# Sitara_IO_Bank_123.net
KiCad netlist of a schematic drawn in Altium Designer
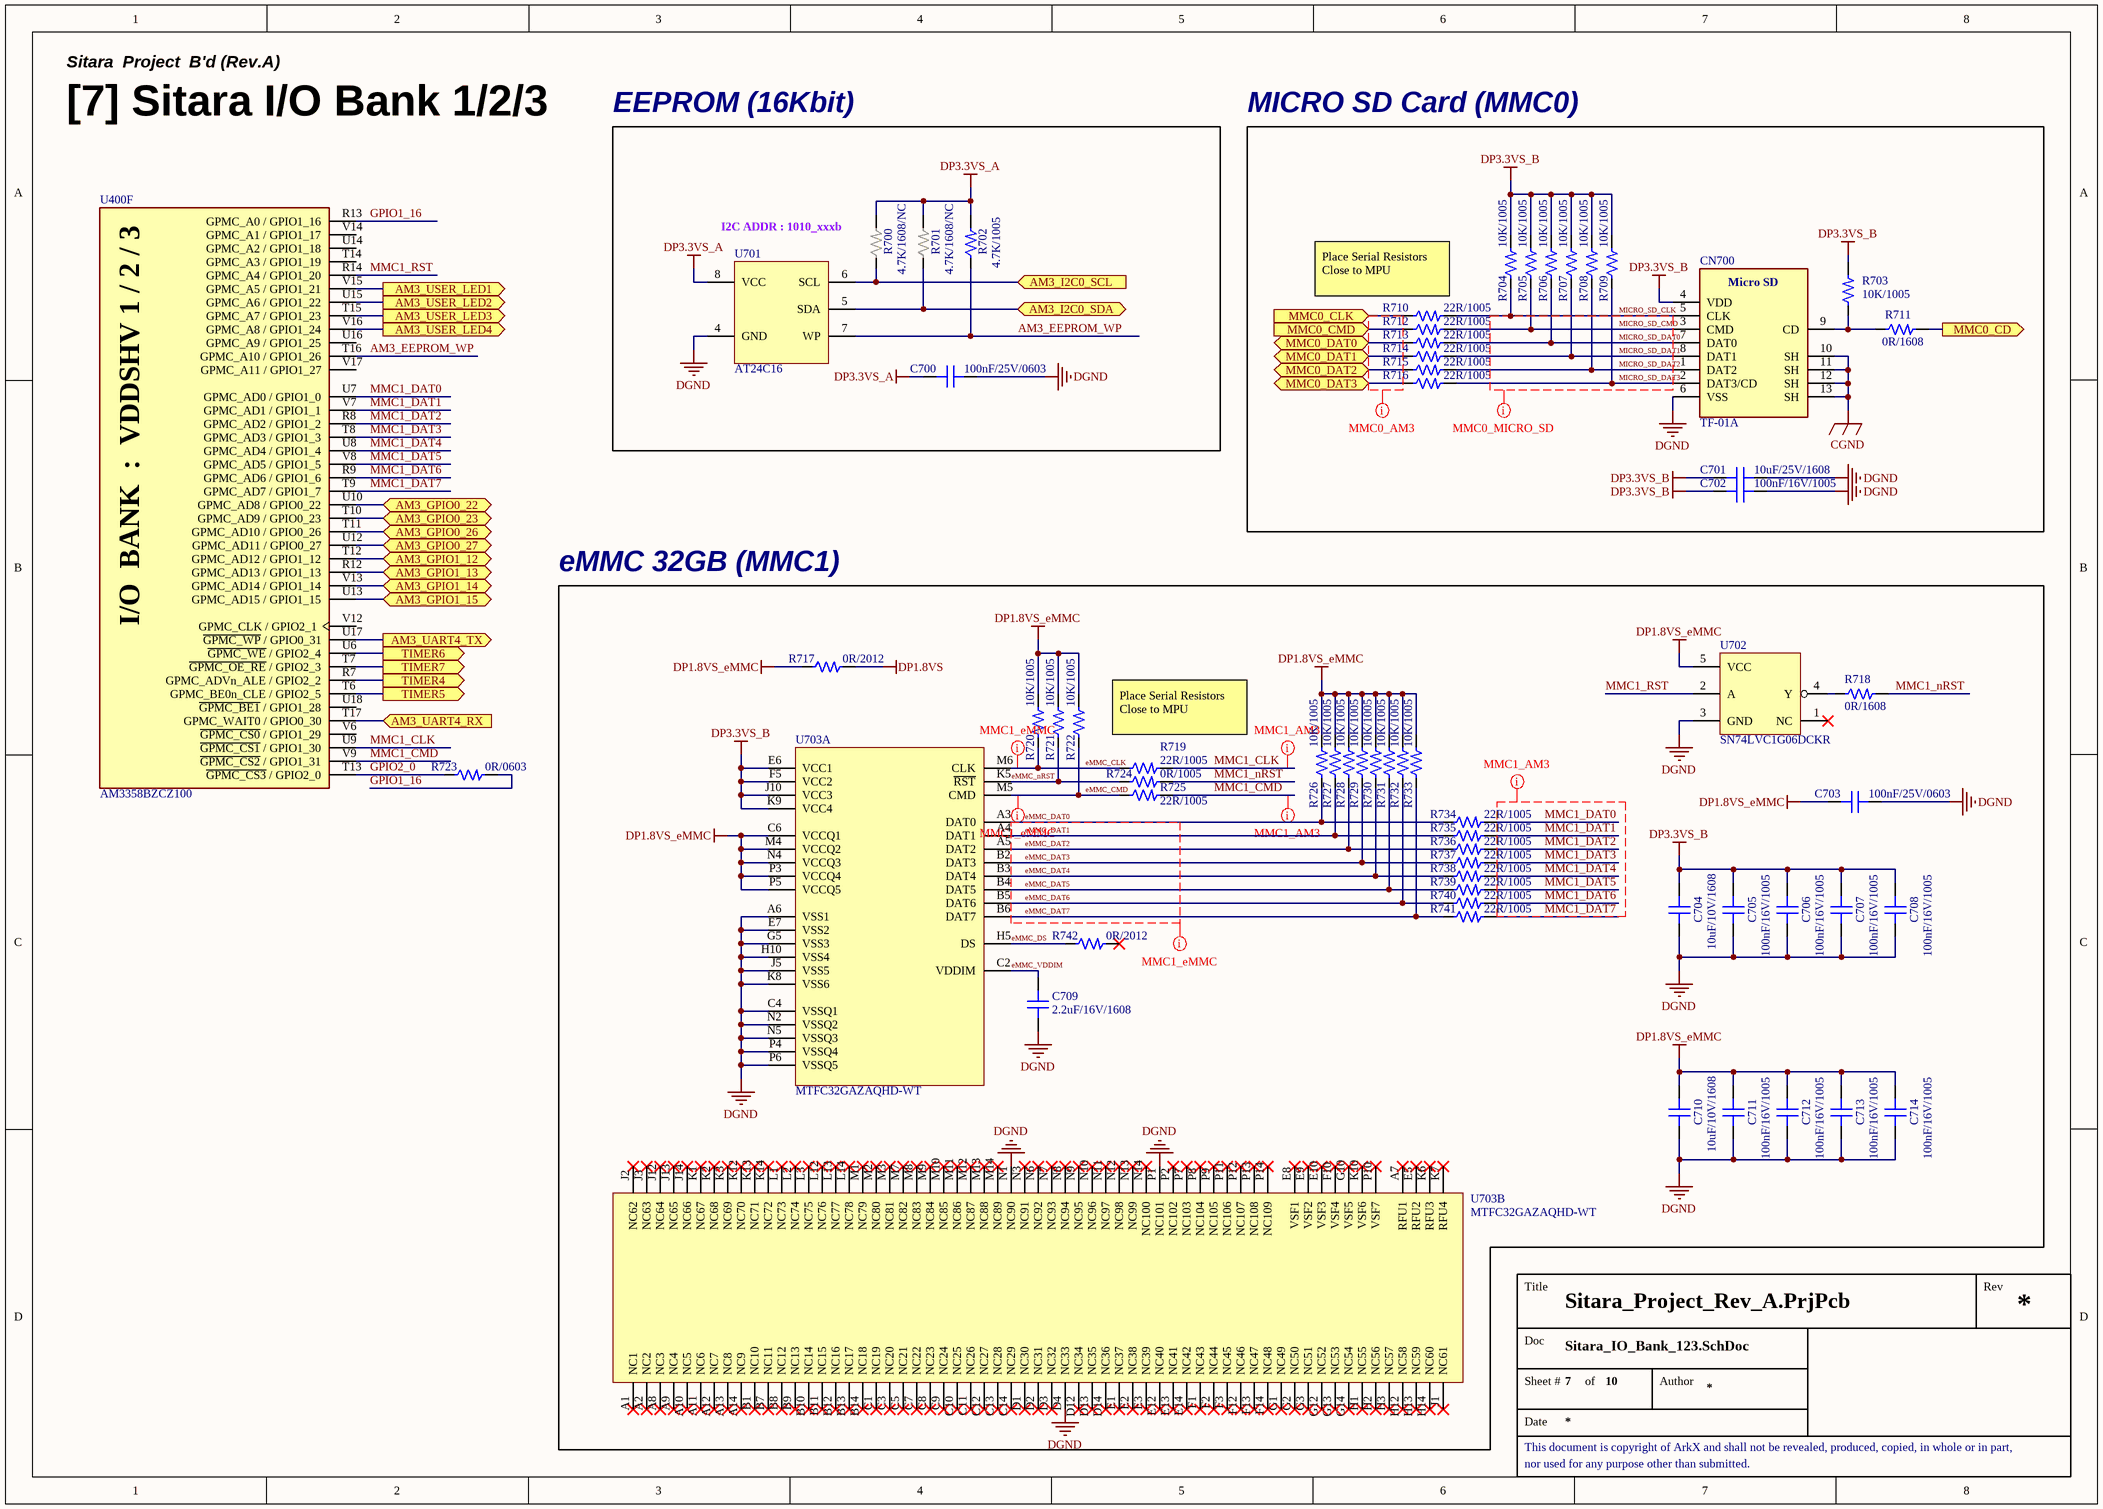
[diagram p0: Sitara_IO_Bank_123.SchDoc]

(export (version "E")
  (design (tool "Eeschema 10.0.6"))
  (components
    (comp (ref "C700")
      (value "100nF/25V/0603")
      (footprint "CAP 0603 (0201_INCH)")
      (description "Ceramic CAP_100nF/25V/0603")
      (fields (field (name "LCSC PART #") "C181047"))
      (libsource (lib "Arkx") (part "CAP_100nF/25V/0603"))
    )
    (comp (ref "C701")
      (value "10uF/25V/1608")
      (footprint "CAP 1608 (0603_INCH)")
      (description "Ceramic CAP_10uF/25V/1608")
      (fields (field (name "LCSC PART #") "C96446"))
      (libsource (lib "Arkx") (part "CAP_10uF/25V/1608"))
    )
    (comp (ref "C702")
      (value "100nF/16V/1005")
      (footprint "CAP 1005 (0402_INCH)")
      (description "Ceramic CAP_100nF/16V/1005")
      (fields (field (name "LCSC PART #") "C1525"))
      (libsource (lib "Arkx") (part "CAP_100nF/16V/1005"))
    )
    (comp (ref "C703")
      (value "100nF/25V/0603")
      (footprint "CAP 0603 (0201_INCH)")
      (description "Ceramic CAP_100nF/25V/0603")
      (fields (field (name "LCSC PART #") "C181047"))
      (libsource (lib "Arkx") (part "CAP_100nF/25V/0603"))
    )
    (comp (ref "C704")
      (value "10uF/10V/1608")
      (footprint "CAP 1608 (0603_INCH)")
      (description "Ceramic CAP_10uF/10V/1608")
      (fields (field (name "LCSC PART #") "C19702"))
      (libsource (lib "Arkx") (part "CAP_10uF/10V/1608"))
    )
    (comp (ref "C705")
      (value "100nF/16V/1005")
      (footprint "CAP 1005 (0402_INCH)")
      (description "Ceramic CAP_100nF/16V/1005")
      (fields (field (name "LCSC PART #") "C1525"))
      (libsource (lib "Arkx") (part "CAP_100nF/16V/1005"))
    )
    (comp (ref "C706")
      (value "100nF/16V/1005")
      (footprint "CAP 1005 (0402_INCH)")
      (description "Ceramic CAP_100nF/16V/1005")
      (fields (field (name "LCSC PART #") "C1525"))
      (libsource (lib "Arkx") (part "CAP_100nF/16V/1005"))
    )
    (comp (ref "C707")
      (value "100nF/16V/1005")
      (footprint "CAP 1005 (0402_INCH)")
      (description "Ceramic CAP_100nF/16V/1005")
      (fields (field (name "LCSC PART #") "C1525"))
      (libsource (lib "Arkx") (part "CAP_100nF/16V/1005"))
    )
    (comp (ref "C708")
      (value "100nF/16V/1005")
      (footprint "CAP 1005 (0402_INCH)")
      (description "Ceramic CAP_100nF/16V/1005")
      (fields (field (name "LCSC PART #") "C1525"))
      (libsource (lib "Arkx") (part "CAP_100nF/16V/1005"))
    )
    (comp (ref "C709")
      (value "2.2uF/16V/1608")
      (footprint "CAP 1608 (0603_INCH)")
      (description "Ceramic CAP_2.2uF/16V/1608")
      (fields (field (name "LCSC PART #") "C23630"))
      (libsource (lib "Arkx") (part "CAP_2.2uF/16V/1608"))
    )
    (comp (ref "C710")
      (value "10uF/10V/1608")
      (footprint "CAP 1608 (0603_INCH)")
      (description "Ceramic CAP_10uF/10V/1608")
      (fields (field (name "LCSC PART #") "C19702"))
      (libsource (lib "Arkx") (part "CAP_10uF/10V/1608"))
    )
    (comp (ref "C711")
      (value "100nF/16V/1005")
      (footprint "CAP 1005 (0402_INCH)")
      (description "Ceramic CAP_100nF/16V/1005")
      (fields (field (name "LCSC PART #") "C1525"))
      (libsource (lib "Arkx") (part "CAP_100nF/16V/1005"))
    )
    (comp (ref "C712")
      (value "100nF/16V/1005")
      (footprint "CAP 1005 (0402_INCH)")
      (description "Ceramic CAP_100nF/16V/1005")
      (fields (field (name "LCSC PART #") "C1525"))
      (libsource (lib "Arkx") (part "CAP_100nF/16V/1005"))
    )
    (comp (ref "C713")
      (value "100nF/16V/1005")
      (footprint "CAP 1005 (0402_INCH)")
      (description "Ceramic CAP_100nF/16V/1005")
      (fields (field (name "LCSC PART #") "C1525"))
      (libsource (lib "Arkx") (part "CAP_100nF/16V/1005"))
    )
    (comp (ref "C714")
      (value "100nF/16V/1005")
      (footprint "CAP 1005 (0402_INCH)")
      (description "Ceramic CAP_100nF/16V/1005")
      (fields (field (name "LCSC PART #") "C1525"))
      (libsource (lib "Arkx") (part "CAP_100nF/16V/1005"))
    )
    (comp (ref "CN700")
      (value "TF-01A")
      (footprint "CON_MICRO-SD_Socket_TF-01A")
      (description "Card Slot MicroSD card (TF card) Self-bouncing SMD SD Card / Memory Card Connector ROHS")
      (fields (field (name "LCSC PART #") "C91145"))
      (libsource (lib "Arkx") (part "CON_MICRO-SD_Socket_TF-01A"))
    )
    (comp (ref "R700")
      (value "4.7K/1608/NC")
      (footprint "RES 1608 (0603_inch)/NC")
      (description "RES_4.7K/1608/0.1W")
      (libsource (lib "Arkx") (part "RES_NC_4.7K/1608/0.1W"))
    )
    (comp (ref "R701")
      (value "4.7K/1608/NC")
      (footprint "RES 1608 (0603_inch)/NC")
      (description "RES_4.7K/1608/0.1W")
      (libsource (lib "Arkx") (part "RES_NC_4.7K/1608/0.1W"))
    )
    (comp (ref "R702")
      (value "4.7K/1005")
      (footprint "RES 1005 (0402_inch)")
      (description "RES_4.7K/1005/62.5mW")
      (fields (field (name "LCSC PART #") "C25900"))
      (libsource (lib "Arkx") (part "RES_4.7K/1005/62.5mW"))
    )
    (comp (ref "R703")
      (value "10K/1005")
      (footprint "RES 1005 (0402_inch)")
      (description "RES_10K/1005/62.5mW")
      (fields (field (name "LCSC PART #") "C25744"))
      (libsource (lib "Arkx") (part "RES_10K/1005/62.5mW"))
    )
    (comp (ref "R704")
      (value "10K/1005")
      (footprint "RES 1005 (0402_inch)")
      (description "RES_10K/1005/62.5mW")
      (fields (field (name "LCSC PART #") "C25744"))
      (libsource (lib "Arkx") (part "RES_10K/1005/62.5mW"))
    )
    (comp (ref "R705")
      (value "10K/1005")
      (footprint "RES 1005 (0402_inch)")
      (description "RES_10K/1005/62.5mW")
      (fields (field (name "LCSC PART #") "C25744"))
      (libsource (lib "Arkx") (part "RES_10K/1005/62.5mW"))
    )
    (comp (ref "R706")
      (value "10K/1005")
      (footprint "RES 1005 (0402_inch)")
      (description "RES_10K/1005/62.5mW")
      (fields (field (name "LCSC PART #") "C25744"))
      (libsource (lib "Arkx") (part "RES_10K/1005/62.5mW"))
    )
    (comp (ref "R707")
      (value "10K/1005")
      (footprint "RES 1005 (0402_inch)")
      (description "RES_10K/1005/62.5mW")
      (fields (field (name "LCSC PART #") "C25744"))
      (libsource (lib "Arkx") (part "RES_10K/1005/62.5mW"))
    )
    (comp (ref "R708")
      (value "10K/1005")
      (footprint "RES 1005 (0402_inch)")
      (description "RES_10K/1005/62.5mW")
      (fields (field (name "LCSC PART #") "C25744"))
      (libsource (lib "Arkx") (part "RES_10K/1005/62.5mW"))
    )
    (comp (ref "R709")
      (value "10K/1005")
      (footprint "RES 1005 (0402_inch)")
      (description "RES_10K/1005/62.5mW")
      (fields (field (name "LCSC PART #") "C25744"))
      (libsource (lib "Arkx") (part "RES_10K/1005/62.5mW"))
    )
    (comp (ref "R710")
      (value "22R/1005")
      (footprint "RES 1005 (0402_inch)")
      (description "RES_22R/1005/62.5mW")
      (fields (field (name "LCSC PART #") "C25092"))
      (libsource (lib "Arkx") (part "RES_22R/1005/62.5mW"))
    )
    (comp (ref "R711")
      (value "0R/1608")
      (footprint "RES 1608 (0603_inch)")
      (description "RES_0R/1608/0.1W")
      (fields (field (name "LCSC PART #") "C21189"))
      (libsource (lib "Arkx") (part "RES_0R/1608/0.1W"))
    )
    (comp (ref "R712")
      (value "22R/1005")
      (footprint "RES 1005 (0402_inch)")
      (description "RES_22R/1005/62.5mW")
      (fields (field (name "LCSC PART #") "C25092"))
      (libsource (lib "Arkx") (part "RES_22R/1005/62.5mW"))
    )
    (comp (ref "R713")
      (value "22R/1005")
      (footprint "RES 1005 (0402_inch)")
      (description "RES_22R/1005/62.5mW")
      (fields (field (name "LCSC PART #") "C25092"))
      (libsource (lib "Arkx") (part "RES_22R/1005/62.5mW"))
    )
    (comp (ref "R714")
      (value "22R/1005")
      (footprint "RES 1005 (0402_inch)")
      (description "RES_22R/1005/62.5mW")
      (fields (field (name "LCSC PART #") "C25092"))
      (libsource (lib "Arkx") (part "RES_22R/1005/62.5mW"))
    )
    (comp (ref "R715")
      (value "22R/1005")
      (footprint "RES 1005 (0402_inch)")
      (description "RES_22R/1005/62.5mW")
      (fields (field (name "LCSC PART #") "C25092"))
      (libsource (lib "Arkx") (part "RES_22R/1005/62.5mW"))
    )
    (comp (ref "R716")
      (value "22R/1005")
      (footprint "RES 1005 (0402_inch)")
      (description "RES_22R/1005/62.5mW")
      (fields (field (name "LCSC PART #") "C25092"))
      (libsource (lib "Arkx") (part "RES_22R/1005/62.5mW"))
    )
    (comp (ref "R717")
      (value "0R/2012")
      (footprint "RES 2012 (0805_inch)")
      (description "RES_0R/2012/0.125W")
      (fields (field (name "LCSC PART #") "C17477"))
      (libsource (lib "Arkx") (part "RES_0R/2012/0.125W"))
    )
    (comp (ref "R718")
      (value "0R/1608")
      (footprint "RES 1608 (0603_inch)")
      (description "RES_0R/1608/0.1W")
      (fields (field (name "LCSC PART #") "C21189"))
      (libsource (lib "Arkx") (part "RES_0R/1608/0.1W"))
    )
    (comp (ref "R719")
      (value "22R/1005")
      (footprint "RES 1005 (0402_inch)")
      (description "RES_22R/1005/62.5mW")
      (fields (field (name "LCSC PART #") "C25092"))
      (libsource (lib "Arkx") (part "RES_22R/1005/62.5mW"))
    )
    (comp (ref "R720")
      (value "10K/1005")
      (footprint "RES 1005 (0402_inch)")
      (description "RES_10K/1005/62.5mW")
      (fields (field (name "LCSC PART #") "C25744"))
      (libsource (lib "Arkx") (part "RES_10K/1005/62.5mW"))
    )
    (comp (ref "R721")
      (value "10K/1005")
      (footprint "RES 1005 (0402_inch)")
      (description "RES_10K/1005/62.5mW")
      (fields (field (name "LCSC PART #") "C25744"))
      (libsource (lib "Arkx") (part "RES_10K/1005/62.5mW"))
    )
    (comp (ref "R722")
      (value "10K/1005")
      (footprint "RES 1005 (0402_inch)")
      (description "RES_10K/1005/62.5mW")
      (fields (field (name "LCSC PART #") "C25744"))
      (libsource (lib "Arkx") (part "RES_10K/1005/62.5mW"))
    )
    (comp (ref "R723")
      (value "0R/0603")
      (footprint "RES 0603 (0201_inch)")
      (description "50mW Thick Film Resistors 25V ±1% 0Ω 0201  Chip Resistor - Surface Mount ROHS")
      (fields (field (name "LCSC PART #") "C106227"))
      (libsource (lib "Arkx") (part "RES_0R/0603/50mW"))
    )
    (comp (ref "R724")
      (value "0R/1005")
      (footprint "RES 1005 (0402_inch)")
      (description "RES_0R/1005/62.5mW")
      (fields (field (name "LCSC PART #") "C17168"))
      (libsource (lib "Arkx") (part "RES_0R/1005/62.5mW"))
    )
    (comp (ref "R725")
      (value "22R/1005")
      (footprint "RES 1005 (0402_inch)")
      (description "RES_22R/1005/62.5mW")
      (fields (field (name "LCSC PART #") "C25092"))
      (libsource (lib "Arkx") (part "RES_22R/1005/62.5mW"))
    )
    (comp (ref "R726")
      (value "10K/1005")
      (footprint "RES 1005 (0402_inch)")
      (description "RES_10K/1005/62.5mW")
      (fields (field (name "LCSC PART #") "C25744"))
      (libsource (lib "Arkx") (part "RES_10K/1005/62.5mW"))
    )
    (comp (ref "R727")
      (value "10K/1005")
      (footprint "RES 1005 (0402_inch)")
      (description "RES_10K/1005/62.5mW")
      (fields (field (name "LCSC PART #") "C25744"))
      (libsource (lib "Arkx") (part "RES_10K/1005/62.5mW"))
    )
    (comp (ref "R728")
      (value "10K/1005")
      (footprint "RES 1005 (0402_inch)")
      (description "RES_10K/1005/62.5mW")
      (fields (field (name "LCSC PART #") "C25744"))
      (libsource (lib "Arkx") (part "RES_10K/1005/62.5mW"))
    )
    (comp (ref "R729")
      (value "10K/1005")
      (footprint "RES 1005 (0402_inch)")
      (description "RES_10K/1005/62.5mW")
      (fields (field (name "LCSC PART #") "C25744"))
      (libsource (lib "Arkx") (part "RES_10K/1005/62.5mW"))
    )
    (comp (ref "R730")
      (value "10K/1005")
      (footprint "RES 1005 (0402_inch)")
      (description "RES_10K/1005/62.5mW")
      (fields (field (name "LCSC PART #") "C25744"))
      (libsource (lib "Arkx") (part "RES_10K/1005/62.5mW"))
    )
    (comp (ref "R731")
      (value "10K/1005")
      (footprint "RES 1005 (0402_inch)")
      (description "RES_10K/1005/62.5mW")
      (fields (field (name "LCSC PART #") "C25744"))
      (libsource (lib "Arkx") (part "RES_10K/1005/62.5mW"))
    )
    (comp (ref "R732")
      (value "10K/1005")
      (footprint "RES 1005 (0402_inch)")
      (description "RES_10K/1005/62.5mW")
      (fields (field (name "LCSC PART #") "C25744"))
      (libsource (lib "Arkx") (part "RES_10K/1005/62.5mW"))
    )
    (comp (ref "R733")
      (value "10K/1005")
      (footprint "RES 1005 (0402_inch)")
      (description "RES_10K/1005/62.5mW")
      (fields (field (name "LCSC PART #") "C25744"))
      (libsource (lib "Arkx") (part "RES_10K/1005/62.5mW"))
    )
    (comp (ref "R734")
      (value "22R/1005")
      (footprint "RES 1005 (0402_inch)")
      (description "RES_22R/1005/62.5mW")
      (fields (field (name "LCSC PART #") "C25092"))
      (libsource (lib "Arkx") (part "RES_22R/1005/62.5mW"))
    )
    (comp (ref "R735")
      (value "22R/1005")
      (footprint "RES 1005 (0402_inch)")
      (description "RES_22R/1005/62.5mW")
      (fields (field (name "LCSC PART #") "C25092"))
      (libsource (lib "Arkx") (part "RES_22R/1005/62.5mW"))
    )
    (comp (ref "R736")
      (value "22R/1005")
      (footprint "RES 1005 (0402_inch)")
      (description "RES_22R/1005/62.5mW")
      (fields (field (name "LCSC PART #") "C25092"))
      (libsource (lib "Arkx") (part "RES_22R/1005/62.5mW"))
    )
    (comp (ref "R737")
      (value "22R/1005")
      (footprint "RES 1005 (0402_inch)")
      (description "RES_22R/1005/62.5mW")
      (fields (field (name "LCSC PART #") "C25092"))
      (libsource (lib "Arkx") (part "RES_22R/1005/62.5mW"))
    )
    (comp (ref "R738")
      (value "22R/1005")
      (footprint "RES 1005 (0402_inch)")
      (description "RES_22R/1005/62.5mW")
      (fields (field (name "LCSC PART #") "C25092"))
      (libsource (lib "Arkx") (part "RES_22R/1005/62.5mW"))
    )
    (comp (ref "R739")
      (value "22R/1005")
      (footprint "RES 1005 (0402_inch)")
      (description "RES_22R/1005/62.5mW")
      (fields (field (name "LCSC PART #") "C25092"))
      (libsource (lib "Arkx") (part "RES_22R/1005/62.5mW"))
    )
    (comp (ref "R740")
      (value "22R/1005")
      (footprint "RES 1005 (0402_inch)")
      (description "RES_22R/1005/62.5mW")
      (fields (field (name "LCSC PART #") "C25092"))
      (libsource (lib "Arkx") (part "RES_22R/1005/62.5mW"))
    )
    (comp (ref "R741")
      (value "22R/1005")
      (footprint "RES 1005 (0402_inch)")
      (description "RES_22R/1005/62.5mW")
      (fields (field (name "LCSC PART #") "C25092"))
      (libsource (lib "Arkx") (part "RES_22R/1005/62.5mW"))
    )
    (comp (ref "R742")
      (value "0R/2012")
      (footprint "RES 2012 (0805_inch)")
      (description "RES_0R/2012/0.125W")
      (fields (field (name "LCSC PART #") "C17477"))
      (libsource (lib "Arkx") (part "RES_0R/2012/0.125W"))
    )
    (comp (ref "U400")
      (value "AM3358BZCZ100")
      (footprint "IC_SOC_AM3358BZCZ100")
      (description "ARM® Cortex®-A8 Microprocessor IC Sitara™ 1 Core, 32-Bit 1.0GHz 324-NFBGA (15x15)")
      (fields (field (name "LCSC PART #") "C73932"))
      (libsource (lib "Arkx") (part "IC_SOC_AM3358BZCZ100"))
    )
    (comp (ref "U701")
      (value "AT24C16")
      (footprint "TSSOP-8_PW (TI)")
      (description "IC EEPROM 16KBIT I2C 1MHZ 8TSSOP")
      (fields (field (name "LCSC PART #") "C112954"))
      (libsource (lib "Arkx") (part "IC_EEPROM_AT24C16"))
    )
    (comp (ref "U702")
      (value "SN74LVC1G06DCKR")
      (footprint "IC_SC-70-5")
      (description "Inverter IC 1 Channel Open Drain SC-70-5")
      (fields (field (name "LCSC PART #") "C7828"))
      (libsource (lib "Arkx") (part "IC_BUF_SN74LVC1G06DCKR"))
    )
    (comp (ref "U703")
      (value "MTFC32GAZAQHD-WT")
      (footprint "IC_VFBGA-153")
      (description "FLASH - NAND Memory IC 256Gbit MMC 200 MHz 153-VFBGA (11.5x13)")
      (fields (field (name "LCSC PART #") "C5330430"))
      (libsource (lib "Arkx") (part "IC_eMMC_MTFC32GAZAQHD-WT"))
    )
  )
  (nets
    (net (code "1") (name "/AM3_EEPROM_WP") (class "Default")
      (node (ref "R702") (pin "1") (pinfunction "1_1") (pintype "passive"))
      (node (ref "U400") (pin "T16") (pinfunction "GPMC_A10_/_GPIO1_26_T16") (pintype "passive"))
      (node (ref "U701") (pin "7") (pinfunction "WP_7") (pintype "passive"))
    )
    (net (code "2") (name "/AM3_GPIO0_22") (class "Default")
      (node (ref "U400") (pin "U10") (pinfunction "GPMC_AD8_/_GPIO0_22_U10") (pintype "passive"))
    )
    (net (code "3") (name "/AM3_GPIO0_23") (class "Default")
      (node (ref "U400") (pin "T10") (pinfunction "GPMC_AD9_/_GPIO0_23_T10") (pintype "passive"))
    )
    (net (code "4") (name "/AM3_GPIO0_26") (class "Default")
      (node (ref "U400") (pin "T11") (pinfunction "GPMC_AD10_/_GPIO0_26_T11") (pintype "passive"))
    )
    (net (code "5") (name "/AM3_GPIO0_27") (class "Default")
      (node (ref "U400") (pin "U12") (pinfunction "GPMC_AD11_/_GPIO0_27_U12") (pintype "passive"))
    )
    (net (code "6") (name "/AM3_GPIO1_12") (class "Default")
      (node (ref "U400") (pin "T12") (pinfunction "GPMC_AD12_/_GPIO1_12_T12") (pintype "passive"))
    )
    (net (code "7") (name "/AM3_GPIO1_13") (class "Default")
      (node (ref "U400") (pin "R12") (pinfunction "GPMC_AD13_/_GPIO1_13_R12") (pintype "passive"))
    )
    (net (code "8") (name "/AM3_GPIO1_14") (class "Default")
      (node (ref "U400") (pin "V13") (pinfunction "GPMC_AD14_/_GPIO1_14_V13") (pintype "passive"))
    )
    (net (code "9") (name "/AM3_GPIO1_15") (class "Default")
      (node (ref "U400") (pin "U13") (pinfunction "GPMC_AD15_/_GPIO1_15_U13") (pintype "passive"))
    )
    (net (code "10") (name "/AM3_I2C0_SCL") (class "Default")
      (node (ref "R700") (pin "1") (pinfunction "1_1") (pintype "passive"))
      (node (ref "U701") (pin "6") (pinfunction "SCL_6") (pintype "passive"))
    )
    (net (code "11") (name "/AM3_I2C0_SDA") (class "Default")
      (node (ref "R701") (pin "1") (pinfunction "1_1") (pintype "passive"))
      (node (ref "U701") (pin "5") (pinfunction "SDA_5") (pintype "passive"))
    )
    (net (code "12") (name "/AM3_UART4_RX") (class "Default")
      (node (ref "U400") (pin "T17") (pinfunction "GPMC_WAIT0_/_GPIO0_30_T17") (pintype "passive"))
    )
    (net (code "13") (name "/AM3_UART4_TX") (class "Default")
      (node (ref "U400") (pin "U17") (pinfunction "~{GPMC_WP}_/_GPIO0_31_U17") (pintype "passive"))
    )
    (net (code "14") (name "/AM3_USER_LED1") (class "Default")
      (node (ref "U400") (pin "V15") (pinfunction "GPMC_A5_/_GPIO1_21_V15") (pintype "passive"))
    )
    (net (code "15") (name "/AM3_USER_LED2") (class "Default")
      (node (ref "U400") (pin "U15") (pinfunction "GPMC_A6_/_GPIO1_22_U15") (pintype "passive"))
    )
    (net (code "16") (name "/AM3_USER_LED3") (class "Default")
      (node (ref "U400") (pin "T15") (pinfunction "GPMC_A7_/_GPIO1_23_T15") (pintype "passive"))
    )
    (net (code "17") (name "/AM3_USER_LED4") (class "Default")
      (node (ref "U400") (pin "V16") (pinfunction "GPMC_A8_/_GPIO1_24_V16") (pintype "passive"))
    )
    (net (code "18") (name "/GPIO1_16") (class "Default")
      (node (ref "R723") (pin "2") (pinfunction "2_2") (pintype "passive"))
      (node (ref "U400") (pin "R13") (pinfunction "GPMC_A0_/_GPIO1_16_R13") (pintype "passive"))
    )
    (net (code "19") (name "/GPIO2_0") (class "Default")
      (node (ref "R723") (pin "1") (pinfunction "1_1") (pintype "passive"))
      (node (ref "U400") (pin "T13") (pinfunction "~{GPMC_CS3}_/_GPIO2_0_T13") (pintype "passive"))
    )
    (net (code "20") (name "/MICRO_SD_CLK") (class "Default")
      (node (ref "CN700") (pin "5") (pinfunction "CLK_5") (pintype "passive"))
      (node (ref "R704") (pin "1") (pinfunction "1_1") (pintype "passive"))
      (node (ref "R710") (pin "2") (pinfunction "2_2") (pintype "passive"))
    )
    (net (code "21") (name "/MICRO_SD_CMD") (class "Default")
      (node (ref "CN700") (pin "3") (pinfunction "CMD_3") (pintype "passive"))
      (node (ref "R705") (pin "1") (pinfunction "1_1") (pintype "passive"))
      (node (ref "R712") (pin "2") (pinfunction "2_2") (pintype "passive"))
    )
    (net (code "22") (name "/MICRO_SD_DAT0") (class "Default")
      (node (ref "CN700") (pin "7") (pinfunction "DAT0_7") (pintype "passive"))
      (node (ref "R706") (pin "1") (pinfunction "1_1") (pintype "passive"))
      (node (ref "R713") (pin "2") (pinfunction "2_2") (pintype "passive"))
    )
    (net (code "23") (name "/MICRO_SD_DAT1") (class "Default")
      (node (ref "CN700") (pin "8") (pinfunction "DAT1_8") (pintype "passive"))
      (node (ref "R707") (pin "1") (pinfunction "1_1") (pintype "passive"))
      (node (ref "R714") (pin "2") (pinfunction "2_2") (pintype "passive"))
    )
    (net (code "24") (name "/MICRO_SD_DAT2") (class "Default")
      (node (ref "CN700") (pin "1") (pinfunction "DAT2_1") (pintype "passive"))
      (node (ref "R708") (pin "1") (pinfunction "1_1") (pintype "passive"))
      (node (ref "R715") (pin "2") (pinfunction "2_2") (pintype "passive"))
    )
    (net (code "25") (name "/MICRO_SD_DAT3") (class "Default")
      (node (ref "CN700") (pin "2") (pinfunction "DAT3/CD_2") (pintype "passive"))
      (node (ref "R709") (pin "1") (pinfunction "1_1") (pintype "passive"))
      (node (ref "R716") (pin "2") (pinfunction "2_2") (pintype "passive"))
    )
    (net (code "26") (name "/MMC0_CD") (class "Default")
      (node (ref "R711") (pin "2") (pinfunction "2_2") (pintype "passive"))
    )
    (net (code "27") (name "/MMC0_CLK") (class "Default")
      (node (ref "R710") (pin "1") (pinfunction "1_1") (pintype "passive"))
    )
    (net (code "28") (name "/MMC0_CMD") (class "Default")
      (node (ref "R712") (pin "1") (pinfunction "1_1") (pintype "passive"))
    )
    (net (code "29") (name "/MMC0_DAT0") (class "Default")
      (node (ref "R713") (pin "1") (pinfunction "1_1") (pintype "passive"))
    )
    (net (code "30") (name "/MMC0_DAT1") (class "Default")
      (node (ref "R714") (pin "1") (pinfunction "1_1") (pintype "passive"))
    )
    (net (code "31") (name "/MMC0_DAT2") (class "Default")
      (node (ref "R715") (pin "1") (pinfunction "1_1") (pintype "passive"))
    )
    (net (code "32") (name "/MMC0_DAT3") (class "Default")
      (node (ref "R716") (pin "1") (pinfunction "1_1") (pintype "passive"))
    )
    (net (code "33") (name "/MMC1_CLK") (class "Default")
      (node (ref "R719") (pin "2") (pinfunction "2_2") (pintype "passive"))
      (node (ref "U400") (pin "U9") (pinfunction "~{GPMC_CS1}_/_GPIO1_30_U9") (pintype "passive"))
    )
    (net (code "34") (name "/MMC1_CMD") (class "Default")
      (node (ref "R725") (pin "2") (pinfunction "2_2") (pintype "passive"))
      (node (ref "U400") (pin "V9") (pinfunction "~{GPMC_CS2}_/_GPIO1_31_V9") (pintype "passive"))
    )
    (net (code "35") (name "/MMC1_DAT0") (class "Default")
      (node (ref "R734") (pin "2") (pinfunction "2_2") (pintype "passive"))
      (node (ref "U400") (pin "U7") (pinfunction "GPMC_AD0_/_GPIO1_0_U7") (pintype "passive"))
    )
    (net (code "36") (name "/MMC1_DAT1") (class "Default")
      (node (ref "R735") (pin "2") (pinfunction "2_2") (pintype "passive"))
      (node (ref "U400") (pin "V7") (pinfunction "GPMC_AD1_/_GPIO1_1_V7") (pintype "passive"))
    )
    (net (code "37") (name "/MMC1_DAT2") (class "Default")
      (node (ref "R736") (pin "2") (pinfunction "2_2") (pintype "passive"))
      (node (ref "U400") (pin "R8") (pinfunction "GPMC_AD2_/_GPIO1_2_R8") (pintype "passive"))
    )
    (net (code "38") (name "/MMC1_DAT3") (class "Default")
      (node (ref "R737") (pin "2") (pinfunction "2_2") (pintype "passive"))
      (node (ref "U400") (pin "T8") (pinfunction "GPMC_AD3_/_GPIO1_3_T8") (pintype "passive"))
    )
    (net (code "39") (name "/MMC1_DAT4") (class "Default")
      (node (ref "R738") (pin "2") (pinfunction "2_2") (pintype "passive"))
      (node (ref "U400") (pin "U8") (pinfunction "GPMC_AD4_/_GPIO1_4_U8") (pintype "passive"))
    )
    (net (code "40") (name "/MMC1_DAT5") (class "Default")
      (node (ref "R739") (pin "2") (pinfunction "2_2") (pintype "passive"))
      (node (ref "U400") (pin "V8") (pinfunction "GPMC_AD5_/_GPIO1_5_V8") (pintype "passive"))
    )
    (net (code "41") (name "/MMC1_DAT6") (class "Default")
      (node (ref "R740") (pin "2") (pinfunction "2_2") (pintype "passive"))
      (node (ref "U400") (pin "R9") (pinfunction "GPMC_AD6_/_GPIO1_6_R9") (pintype "passive"))
    )
    (net (code "42") (name "/MMC1_DAT7") (class "Default")
      (node (ref "R741") (pin "2") (pinfunction "2_2") (pintype "passive"))
      (node (ref "U400") (pin "T9") (pinfunction "GPMC_AD7_/_GPIO1_7_T9") (pintype "passive"))
    )
    (net (code "43") (name "/MMC1_RST") (class "Default")
      (node (ref "U400") (pin "R14") (pinfunction "GPMC_A4_/_GPIO1_20_R14") (pintype "passive"))
      (node (ref "U702") (pin "2") (pinfunction "A_2") (pintype "passive"))
    )
    (net (code "44") (name "/MMC1_nRST") (class "Default")
      (node (ref "R718") (pin "2") (pinfunction "2_2") (pintype "passive"))
      (node (ref "R724") (pin "2") (pinfunction "2_2") (pintype "passive"))
    )
    (net (code "45") (name "/TIMER4") (class "Default")
      (node (ref "U400") (pin "R7") (pinfunction "GPMC_ADVn_ALE_/_GPIO2_2_R7") (pintype "passive"))
    )
    (net (code "46") (name "/TIMER5") (class "Default")
      (node (ref "U400") (pin "T6") (pinfunction "GPMC_BE0n_CLE_/_GPIO2_5_T6") (pintype "passive"))
    )
    (net (code "47") (name "/TIMER6") (class "Default")
      (node (ref "U400") (pin "U6") (pinfunction "~{GPMC_WE}_/_GPIO2_4_U6") (pintype "passive"))
    )
    (net (code "48") (name "/TIMER7") (class "Default")
      (node (ref "U400") (pin "T7") (pinfunction "~{GPMC_OE_RE}_/_GPIO2_3_T7") (pintype "passive"))
    )
    (net (code "49") (name "/eMMC_CLK") (class "Default")
      (node (ref "R719") (pin "1") (pinfunction "1_1") (pintype "passive"))
      (node (ref "R720") (pin "1") (pinfunction "1_1") (pintype "passive"))
      (node (ref "U703") (pin "M6") (pinfunction "CLK_M6") (pintype "passive"))
    )
    (net (code "50") (name "/eMMC_CMD") (class "Default")
      (node (ref "R722") (pin "1") (pinfunction "1_1") (pintype "passive"))
      (node (ref "R725") (pin "1") (pinfunction "1_1") (pintype "passive"))
      (node (ref "U703") (pin "M5") (pinfunction "CMD_M5") (pintype "passive"))
    )
    (net (code "51") (name "/eMMC_DAT0") (class "Default")
      (node (ref "R726") (pin "1") (pinfunction "1_1") (pintype "passive"))
      (node (ref "R734") (pin "1") (pinfunction "1_1") (pintype "passive"))
      (node (ref "U703") (pin "A3") (pinfunction "DAT0_A3") (pintype "passive"))
    )
    (net (code "52") (name "/eMMC_DAT1") (class "Default")
      (node (ref "R727") (pin "1") (pinfunction "1_1") (pintype "passive"))
      (node (ref "R735") (pin "1") (pinfunction "1_1") (pintype "passive"))
      (node (ref "U703") (pin "A4") (pinfunction "DAT1_A4") (pintype "passive"))
    )
    (net (code "53") (name "/eMMC_DAT2") (class "Default")
      (node (ref "R728") (pin "1") (pinfunction "1_1") (pintype "passive"))
      (node (ref "R736") (pin "1") (pinfunction "1_1") (pintype "passive"))
      (node (ref "U703") (pin "A5") (pinfunction "DAT2_A5") (pintype "passive"))
    )
    (net (code "54") (name "/eMMC_DAT3") (class "Default")
      (node (ref "R729") (pin "1") (pinfunction "1_1") (pintype "passive"))
      (node (ref "R737") (pin "1") (pinfunction "1_1") (pintype "passive"))
      (node (ref "U703") (pin "B2") (pinfunction "DAT3_B2") (pintype "passive"))
    )
    (net (code "55") (name "/eMMC_DAT4") (class "Default")
      (node (ref "R730") (pin "1") (pinfunction "1_1") (pintype "passive"))
      (node (ref "R738") (pin "1") (pinfunction "1_1") (pintype "passive"))
      (node (ref "U703") (pin "B3") (pinfunction "DAT4_B3") (pintype "passive"))
    )
    (net (code "56") (name "/eMMC_DAT5") (class "Default")
      (node (ref "R731") (pin "1") (pinfunction "1_1") (pintype "passive"))
      (node (ref "R739") (pin "1") (pinfunction "1_1") (pintype "passive"))
      (node (ref "U703") (pin "B4") (pinfunction "DAT5_B4") (pintype "passive"))
    )
    (net (code "57") (name "/eMMC_DAT6") (class "Default")
      (node (ref "R732") (pin "1") (pinfunction "1_1") (pintype "passive"))
      (node (ref "R740") (pin "1") (pinfunction "1_1") (pintype "passive"))
      (node (ref "U703") (pin "B5") (pinfunction "DAT6_B5") (pintype "passive"))
    )
    (net (code "58") (name "/eMMC_DAT7") (class "Default")
      (node (ref "R733") (pin "1") (pinfunction "1_1") (pintype "passive"))
      (node (ref "R741") (pin "1") (pinfunction "1_1") (pintype "passive"))
      (node (ref "U703") (pin "B6") (pinfunction "DAT7_B6") (pintype "passive"))
    )
    (net (code "59") (name "/eMMC_DS") (class "Default")
      (node (ref "R742") (pin "1") (pinfunction "1_1") (pintype "passive"))
      (node (ref "U703") (pin "H5") (pinfunction "DS_H5") (pintype "passive"))
    )
    (net (code "60") (name "/eMMC_VDDIM") (class "Default")
      (node (ref "C709") (pin "2") (pinfunction "2_2") (pintype "passive"))
      (node (ref "U703") (pin "C2") (pinfunction "VDDIM_C2") (pintype "passive"))
    )
    (net (code "61") (name "/eMMC_nRST") (class "Default")
      (node (ref "R721") (pin "1") (pinfunction "1_1") (pintype "passive"))
      (node (ref "R724") (pin "1") (pinfunction "1_1") (pintype "passive"))
      (node (ref "U703") (pin "K5") (pinfunction "~{RST}_K5") (pintype "passive"))
    )
    (net (code "62") (name "CGND") (class "Default")
      (node (ref "CN700") (pin "10") (pinfunction "SH_10") (pintype "passive"))
      (node (ref "CN700") (pin "11") (pinfunction "SH_11") (pintype "passive"))
      (node (ref "CN700") (pin "12") (pinfunction "SH_12") (pintype "passive"))
      (node (ref "CN700") (pin "13") (pinfunction "SH_13") (pintype "passive"))
    )
    (net (code "63") (name "DGND") (class "Default")
      (node (ref "C700") (pin "2") (pinfunction "2_2") (pintype "passive"))
      (node (ref "C701") (pin "2") (pinfunction "2_2") (pintype "passive"))
      (node (ref "C702") (pin "2") (pinfunction "2_2") (pintype "passive"))
      (node (ref "C703") (pin "2") (pinfunction "2_2") (pintype "passive"))
      (node (ref "C704") (pin "1") (pinfunction "1_1") (pintype "passive"))
      (node (ref "C705") (pin "1") (pinfunction "1_1") (pintype "passive"))
      (node (ref "C706") (pin "1") (pinfunction "1_1") (pintype "passive"))
      (node (ref "C707") (pin "1") (pinfunction "1_1") (pintype "passive"))
      (node (ref "C708") (pin "1") (pinfunction "1_1") (pintype "passive"))
      (node (ref "C709") (pin "1") (pinfunction "1_1") (pintype "passive"))
      (node (ref "C710") (pin "1") (pinfunction "1_1") (pintype "passive"))
      (node (ref "C711") (pin "1") (pinfunction "1_1") (pintype "passive"))
      (node (ref "C712") (pin "1") (pinfunction "1_1") (pintype "passive"))
      (node (ref "C713") (pin "1") (pinfunction "1_1") (pintype "passive"))
      (node (ref "C714") (pin "1") (pinfunction "1_1") (pintype "passive"))
      (node (ref "CN700") (pin "6") (pinfunction "VSS_6") (pintype "passive"))
      (node (ref "U701") (pin "4") (pinfunction "GND_4") (pintype "passive"))
      (node (ref "U702") (pin "3") (pinfunction "GND_3") (pintype "passive"))
      (node (ref "U703") (pin "A6") (pinfunction "VSS1_A6") (pintype "passive"))
      (node (ref "U703") (pin "C4") (pinfunction "VSSQ1_C4") (pintype "passive"))
      (node (ref "U703") (pin "D4") (pinfunction "NC33_D4") (pintype "passive"))
      (node (ref "U703") (pin "E7") (pinfunction "VSS2_E7") (pintype "passive"))
      (node (ref "U703") (pin "G5") (pinfunction "VSS3_G5") (pintype "passive"))
      (node (ref "U703") (pin "H10") (pinfunction "VSS4_H10") (pintype "passive"))
      (node (ref "U703") (pin "J5") (pinfunction "VSS5_J5") (pintype "passive"))
      (node (ref "U703") (pin "K8") (pinfunction "VSS6_K8") (pintype "passive"))
      (node (ref "U703") (pin "N1") (pinfunction "NC90_N1") (pintype "passive"))
      (node (ref "U703") (pin "N2") (pinfunction "VSSQ2_N2") (pintype "passive"))
      (node (ref "U703") (pin "N5") (pinfunction "VSSQ3_N5") (pintype "passive"))
      (node (ref "U703") (pin "P1") (pinfunction "NC101_P1") (pintype "passive"))
      (node (ref "U703") (pin "P4") (pinfunction "VSSQ4_P4") (pintype "passive"))
      (node (ref "U703") (pin "P6") (pinfunction "VSSQ5_P6") (pintype "passive"))
    )
    (net (code "64") (name "DP1.8VS") (class "Default")
      (node (ref "R717") (pin "2") (pinfunction "2_2") (pintype "passive"))
    )
    (net (code "65") (name "DP1.8VS_eMMC") (class "Default")
      (node (ref "C703") (pin "1") (pinfunction "1_1") (pintype "passive"))
      (node (ref "C710") (pin "2") (pinfunction "2_2") (pintype "passive"))
      (node (ref "C711") (pin "2") (pinfunction "2_2") (pintype "passive"))
      (node (ref "C712") (pin "2") (pinfunction "2_2") (pintype "passive"))
      (node (ref "C713") (pin "2") (pinfunction "2_2") (pintype "passive"))
      (node (ref "C714") (pin "2") (pinfunction "2_2") (pintype "passive"))
      (node (ref "R717") (pin "1") (pinfunction "1_1") (pintype "passive"))
      (node (ref "R720") (pin "2") (pinfunction "2_2") (pintype "passive"))
      (node (ref "R721") (pin "2") (pinfunction "2_2") (pintype "passive"))
      (node (ref "R722") (pin "2") (pinfunction "2_2") (pintype "passive"))
      (node (ref "R726") (pin "2") (pinfunction "2_2") (pintype "passive"))
      (node (ref "R727") (pin "2") (pinfunction "2_2") (pintype "passive"))
      (node (ref "R728") (pin "2") (pinfunction "2_2") (pintype "passive"))
      (node (ref "R729") (pin "2") (pinfunction "2_2") (pintype "passive"))
      (node (ref "R730") (pin "2") (pinfunction "2_2") (pintype "passive"))
      (node (ref "R731") (pin "2") (pinfunction "2_2") (pintype "passive"))
      (node (ref "R732") (pin "2") (pinfunction "2_2") (pintype "passive"))
      (node (ref "R733") (pin "2") (pinfunction "2_2") (pintype "passive"))
      (node (ref "U702") (pin "5") (pinfunction "VCC_5") (pintype "passive"))
      (node (ref "U703") (pin "C6") (pinfunction "VCCQ1_C6") (pintype "passive"))
      (node (ref "U703") (pin "M4") (pinfunction "VCCQ2_M4") (pintype "passive"))
      (node (ref "U703") (pin "N4") (pinfunction "VCCQ3_N4") (pintype "passive"))
      (node (ref "U703") (pin "P3") (pinfunction "VCCQ4_P3") (pintype "passive"))
      (node (ref "U703") (pin "P5") (pinfunction "VCCQ5_P5") (pintype "passive"))
    )
    (net (code "66") (name "DP3.3VS_A") (class "Default")
      (node (ref "C700") (pin "1") (pinfunction "1_1") (pintype "passive"))
      (node (ref "R700") (pin "2") (pinfunction "2_2") (pintype "passive"))
      (node (ref "R701") (pin "2") (pinfunction "2_2") (pintype "passive"))
      (node (ref "R702") (pin "2") (pinfunction "2_2") (pintype "passive"))
      (node (ref "U701") (pin "8") (pinfunction "VCC_8") (pintype "passive"))
    )
    (net (code "67") (name "DP3.3VS_B") (class "Default")
      (node (ref "C701") (pin "1") (pinfunction "1_1") (pintype "passive"))
      (node (ref "C702") (pin "1") (pinfunction "1_1") (pintype "passive"))
      (node (ref "C704") (pin "2") (pinfunction "2_2") (pintype "passive"))
      (node (ref "C705") (pin "2") (pinfunction "2_2") (pintype "passive"))
      (node (ref "C706") (pin "2") (pinfunction "2_2") (pintype "passive"))
      (node (ref "C707") (pin "2") (pinfunction "2_2") (pintype "passive"))
      (node (ref "C708") (pin "2") (pinfunction "2_2") (pintype "passive"))
      (node (ref "CN700") (pin "4") (pinfunction "VDD_4") (pintype "passive"))
      (node (ref "R703") (pin "2") (pinfunction "2_2") (pintype "passive"))
      (node (ref "R704") (pin "2") (pinfunction "2_2") (pintype "passive"))
      (node (ref "R705") (pin "2") (pinfunction "2_2") (pintype "passive"))
      (node (ref "R706") (pin "2") (pinfunction "2_2") (pintype "passive"))
      (node (ref "R707") (pin "2") (pinfunction "2_2") (pintype "passive"))
      (node (ref "R708") (pin "2") (pinfunction "2_2") (pintype "passive"))
      (node (ref "R709") (pin "2") (pinfunction "2_2") (pintype "passive"))
      (node (ref "U703") (pin "E6") (pinfunction "VCC1_E6") (pintype "passive"))
      (node (ref "U703") (pin "F5") (pinfunction "VCC2_F5") (pintype "passive"))
      (node (ref "U703") (pin "J10") (pinfunction "VCC3_J10") (pintype "passive"))
      (node (ref "U703") (pin "K9") (pinfunction "VCC4_K9") (pintype "passive"))
    )
    (net (code "68") (name "Net-(CN700-CD)") (class "Default")
      (node (ref "CN700") (pin "9") (pinfunction "CD_9") (pintype "passive"))
      (node (ref "R703") (pin "1") (pinfunction "1_1") (pintype "passive"))
      (node (ref "R711") (pin "1") (pinfunction "1_1") (pintype "passive"))
    )
    (net (code "69") (name "Net-(U702-Y)") (class "Default")
      (node (ref "R718") (pin "1") (pinfunction "1_1") (pintype "passive"))
      (node (ref "U702") (pin "4") (pinfunction "Y_4") (pintype "passive"))
    )
    (net (code "70") (name "unconnected-(R742-Pad2)") (class "Default")
      (node (ref "R742") (pin "2") (pinfunction "2_2") (pintype "passive+no_connect"))
    )
    (net (code "71") (name "unconnected-(U400F-GPMC_A1_{slash}_GPIO1_17-PadV14)") (class "Default")
      (node (ref "U400") (pin "V14") (pinfunction "GPMC_A1_/_GPIO1_17_V14") (pintype "passive"))
    )
    (net (code "72") (name "unconnected-(U400F-GPMC_A2_{slash}_GPIO1_18-PadU14)") (class "Default")
      (node (ref "U400") (pin "U14") (pinfunction "GPMC_A2_/_GPIO1_18_U14") (pintype "passive"))
    )
    (net (code "73") (name "unconnected-(U400F-GPMC_A3_{slash}_GPIO1_19-PadT14)") (class "Default")
      (node (ref "U400") (pin "T14") (pinfunction "GPMC_A3_/_GPIO1_19_T14") (pintype "passive"))
    )
    (net (code "74") (name "unconnected-(U400F-GPMC_A9_{slash}_GPIO1_25-PadU16)") (class "Default")
      (node (ref "U400") (pin "U16") (pinfunction "GPMC_A9_/_GPIO1_25_U16") (pintype "passive"))
    )
    (net (code "75") (name "unconnected-(U400F-GPMC_A11_{slash}_GPIO1_27-PadV17)") (class "Default")
      (node (ref "U400") (pin "V17") (pinfunction "GPMC_A11_/_GPIO1_27_V17") (pintype "passive"))
    )
    (net (code "76") (name "unconnected-(U400F-GPMC_CLK_{slash}_GPIO2_1-PadV12)") (class "Default")
      (node (ref "U400") (pin "V12") (pinfunction "GPMC_CLK_/_GPIO2_1_V12") (pintype "passive"))
    )
    (net (code "77") (name "unconnected-(U400F-~{GPMC_BE1}_{slash}_GPIO1_28-PadU18)") (class "Default")
      (node (ref "U400") (pin "U18") (pinfunction "~{GPMC_BE1}_/_GPIO1_28_U18") (pintype "passive"))
    )
    (net (code "78") (name "unconnected-(U400F-~{GPMC_CS0}_{slash}_GPIO1_29-PadV6)") (class "Default")
      (node (ref "U400") (pin "V6") (pinfunction "~{GPMC_CS0}_/_GPIO1_29_V6") (pintype "passive"))
    )
    (net (code "79") (name "unconnected-(U702-NC-Pad1)") (class "Default")
      (node (ref "U702") (pin "1") (pinfunction "NC_1") (pintype "passive+no_connect"))
    )
    (net (code "80") (name "unconnected-(U703B-NC1-PadA1)") (class "Default")
      (node (ref "U703") (pin "A1") (pinfunction "NC1_A1") (pintype "passive+no_connect"))
    )
    (net (code "81") (name "unconnected-(U703B-NC2-PadA2)") (class "Default")
      (node (ref "U703") (pin "A2") (pinfunction "NC2_A2") (pintype "passive+no_connect"))
    )
    (net (code "82") (name "unconnected-(U703B-NC3-PadA8)") (class "Default")
      (node (ref "U703") (pin "A8") (pinfunction "NC3_A8") (pintype "passive+no_connect"))
    )
    (net (code "83") (name "unconnected-(U703B-NC4-PadA9)") (class "Default")
      (node (ref "U703") (pin "A9") (pinfunction "NC4_A9") (pintype "passive+no_connect"))
    )
    (net (code "84") (name "unconnected-(U703B-NC5-PadA10)") (class "Default")
      (node (ref "U703") (pin "A10") (pinfunction "NC5_A10") (pintype "passive+no_connect"))
    )
    (net (code "85") (name "unconnected-(U703B-NC6-PadA11)") (class "Default")
      (node (ref "U703") (pin "A11") (pinfunction "NC6_A11") (pintype "passive+no_connect"))
    )
    (net (code "86") (name "unconnected-(U703B-NC7-PadA12)") (class "Default")
      (node (ref "U703") (pin "A12") (pinfunction "NC7_A12") (pintype "passive+no_connect"))
    )
    (net (code "87") (name "unconnected-(U703B-NC8-PadA13)") (class "Default")
      (node (ref "U703") (pin "A13") (pinfunction "NC8_A13") (pintype "passive+no_connect"))
    )
    (net (code "88") (name "unconnected-(U703B-NC9-PadA14)") (class "Default")
      (node (ref "U703") (pin "A14") (pinfunction "NC9_A14") (pintype "passive+no_connect"))
    )
    (net (code "89") (name "unconnected-(U703B-NC10-PadB1)") (class "Default")
      (node (ref "U703") (pin "B1") (pinfunction "NC10_B1") (pintype "passive+no_connect"))
    )
    (net (code "90") (name "unconnected-(U703B-NC11-PadB7)") (class "Default")
      (node (ref "U703") (pin "B7") (pinfunction "NC11_B7") (pintype "passive+no_connect"))
    )
    (net (code "91") (name "unconnected-(U703B-NC12-PadB8)") (class "Default")
      (node (ref "U703") (pin "B8") (pinfunction "NC12_B8") (pintype "passive+no_connect"))
    )
    (net (code "92") (name "unconnected-(U703B-NC13-PadB9)") (class "Default")
      (node (ref "U703") (pin "B9") (pinfunction "NC13_B9") (pintype "passive+no_connect"))
    )
    (net (code "93") (name "unconnected-(U703B-NC14-PadB10)") (class "Default")
      (node (ref "U703") (pin "B10") (pinfunction "NC14_B10") (pintype "passive+no_connect"))
    )
    (net (code "94") (name "unconnected-(U703B-NC15-PadB11)") (class "Default")
      (node (ref "U703") (pin "B11") (pinfunction "NC15_B11") (pintype "passive+no_connect"))
    )
    (net (code "95") (name "unconnected-(U703B-NC16-PadB12)") (class "Default")
      (node (ref "U703") (pin "B12") (pinfunction "NC16_B12") (pintype "passive+no_connect"))
    )
    (net (code "96") (name "unconnected-(U703B-NC17-PadB13)") (class "Default")
      (node (ref "U703") (pin "B13") (pinfunction "NC17_B13") (pintype "passive+no_connect"))
    )
    (net (code "97") (name "unconnected-(U703B-NC18-PadB14)") (class "Default")
      (node (ref "U703") (pin "B14") (pinfunction "NC18_B14") (pintype "passive+no_connect"))
    )
    (net (code "98") (name "unconnected-(U703B-NC19-PadC1)") (class "Default")
      (node (ref "U703") (pin "C1") (pinfunction "NC19_C1") (pintype "passive+no_connect"))
    )
    (net (code "99") (name "unconnected-(U703B-NC20-PadC3)") (class "Default")
      (node (ref "U703") (pin "C3") (pinfunction "NC20_C3") (pintype "passive+no_connect"))
    )
    (net (code "100") (name "unconnected-(U703B-NC21-PadC5)") (class "Default")
      (node (ref "U703") (pin "C5") (pinfunction "NC21_C5") (pintype "passive+no_connect"))
    )
    (net (code "101") (name "unconnected-(U703B-NC22-PadC7)") (class "Default")
      (node (ref "U703") (pin "C7") (pinfunction "NC22_C7") (pintype "passive+no_connect"))
    )
    (net (code "102") (name "unconnected-(U703B-NC23-PadC8)") (class "Default")
      (node (ref "U703") (pin "C8") (pinfunction "NC23_C8") (pintype "passive+no_connect"))
    )
    (net (code "103") (name "unconnected-(U703B-NC24-PadC9)") (class "Default")
      (node (ref "U703") (pin "C9") (pinfunction "NC24_C9") (pintype "passive+no_connect"))
    )
    (net (code "104") (name "unconnected-(U703B-NC25-PadC10)") (class "Default")
      (node (ref "U703") (pin "C10") (pinfunction "NC25_C10") (pintype "passive+no_connect"))
    )
    (net (code "105") (name "unconnected-(U703B-NC26-PadC11)") (class "Default")
      (node (ref "U703") (pin "C11") (pinfunction "NC26_C11") (pintype "passive+no_connect"))
    )
    (net (code "106") (name "unconnected-(U703B-NC27-PadC12)") (class "Default")
      (node (ref "U703") (pin "C12") (pinfunction "NC27_C12") (pintype "passive+no_connect"))
    )
    (net (code "107") (name "unconnected-(U703B-NC28-PadC13)") (class "Default")
      (node (ref "U703") (pin "C13") (pinfunction "NC28_C13") (pintype "passive+no_connect"))
    )
    (net (code "108") (name "unconnected-(U703B-NC29-PadC14)") (class "Default")
      (node (ref "U703") (pin "C14") (pinfunction "NC29_C14") (pintype "passive+no_connect"))
    )
    (net (code "109") (name "unconnected-(U703B-NC30-PadD1)") (class "Default")
      (node (ref "U703") (pin "D1") (pinfunction "NC30_D1") (pintype "passive+no_connect"))
    )
    (net (code "110") (name "unconnected-(U703B-NC31-PadD2)") (class "Default")
      (node (ref "U703") (pin "D2") (pinfunction "NC31_D2") (pintype "passive+no_connect"))
    )
    (net (code "111") (name "unconnected-(U703B-NC32-PadD3)") (class "Default")
      (node (ref "U703") (pin "D3") (pinfunction "NC32_D3") (pintype "passive+no_connect"))
    )
    (net (code "112") (name "unconnected-(U703B-NC34-PadD12)") (class "Default")
      (node (ref "U703") (pin "D12") (pinfunction "NC34_D12") (pintype "passive+no_connect"))
    )
    (net (code "113") (name "unconnected-(U703B-NC35-PadD13)") (class "Default")
      (node (ref "U703") (pin "D13") (pinfunction "NC35_D13") (pintype "passive+no_connect"))
    )
    (net (code "114") (name "unconnected-(U703B-NC36-PadD14)") (class "Default")
      (node (ref "U703") (pin "D14") (pinfunction "NC36_D14") (pintype "passive+no_connect"))
    )
    (net (code "115") (name "unconnected-(U703B-NC37-PadE1)") (class "Default")
      (node (ref "U703") (pin "E1") (pinfunction "NC37_E1") (pintype "passive+no_connect"))
    )
    (net (code "116") (name "unconnected-(U703B-NC38-PadE2)") (class "Default")
      (node (ref "U703") (pin "E2") (pinfunction "NC38_E2") (pintype "passive+no_connect"))
    )
    (net (code "117") (name "unconnected-(U703B-NC39-PadE3)") (class "Default")
      (node (ref "U703") (pin "E3") (pinfunction "NC39_E3") (pintype "passive+no_connect"))
    )
    (net (code "118") (name "unconnected-(U703B-NC40-PadE12)") (class "Default")
      (node (ref "U703") (pin "E12") (pinfunction "NC40_E12") (pintype "passive+no_connect"))
    )
    (net (code "119") (name "unconnected-(U703B-NC41-PadE13)") (class "Default")
      (node (ref "U703") (pin "E13") (pinfunction "NC41_E13") (pintype "passive+no_connect"))
    )
    (net (code "120") (name "unconnected-(U703B-NC42-PadE14)") (class "Default")
      (node (ref "U703") (pin "E14") (pinfunction "NC42_E14") (pintype "passive+no_connect"))
    )
    (net (code "121") (name "unconnected-(U703B-NC43-PadF1)") (class "Default")
      (node (ref "U703") (pin "F1") (pinfunction "NC43_F1") (pintype "passive+no_connect"))
    )
    (net (code "122") (name "unconnected-(U703B-NC44-PadF2)") (class "Default")
      (node (ref "U703") (pin "F2") (pinfunction "NC44_F2") (pintype "passive+no_connect"))
    )
    (net (code "123") (name "unconnected-(U703B-NC45-PadF3)") (class "Default")
      (node (ref "U703") (pin "F3") (pinfunction "NC45_F3") (pintype "passive+no_connect"))
    )
    (net (code "124") (name "unconnected-(U703B-NC46-PadF12)") (class "Default")
      (node (ref "U703") (pin "F12") (pinfunction "NC46_F12") (pintype "passive+no_connect"))
    )
    (net (code "125") (name "unconnected-(U703B-NC47-PadF13)") (class "Default")
      (node (ref "U703") (pin "F13") (pinfunction "NC47_F13") (pintype "passive+no_connect"))
    )
    (net (code "126") (name "unconnected-(U703B-NC48-PadF14)") (class "Default")
      (node (ref "U703") (pin "F14") (pinfunction "NC48_F14") (pintype "passive+no_connect"))
    )
    (net (code "127") (name "unconnected-(U703B-NC49-PadG1)") (class "Default")
      (node (ref "U703") (pin "G1") (pinfunction "NC49_G1") (pintype "passive+no_connect"))
    )
    (net (code "128") (name "unconnected-(U703B-NC50-PadG2)") (class "Default")
      (node (ref "U703") (pin "G2") (pinfunction "NC50_G2") (pintype "passive+no_connect"))
    )
    (net (code "129") (name "unconnected-(U703B-NC51-PadG3)") (class "Default")
      (node (ref "U703") (pin "G3") (pinfunction "NC51_G3") (pintype "passive+no_connect"))
    )
    (net (code "130") (name "unconnected-(U703B-NC52-PadG12)") (class "Default")
      (node (ref "U703") (pin "G12") (pinfunction "NC52_G12") (pintype "passive+no_connect"))
    )
    (net (code "131") (name "unconnected-(U703B-NC53-PadG13)") (class "Default")
      (node (ref "U703") (pin "G13") (pinfunction "NC53_G13") (pintype "passive+no_connect"))
    )
    (net (code "132") (name "unconnected-(U703B-NC54-PadG14)") (class "Default")
      (node (ref "U703") (pin "G14") (pinfunction "NC54_G14") (pintype "passive+no_connect"))
    )
    (net (code "133") (name "unconnected-(U703B-NC55-PadH1)") (class "Default")
      (node (ref "U703") (pin "H1") (pinfunction "NC55_H1") (pintype "passive+no_connect"))
    )
    (net (code "134") (name "unconnected-(U703B-NC56-PadH2)") (class "Default")
      (node (ref "U703") (pin "H2") (pinfunction "NC56_H2") (pintype "passive+no_connect"))
    )
    (net (code "135") (name "unconnected-(U703B-NC57-PadH3)") (class "Default")
      (node (ref "U703") (pin "H3") (pinfunction "NC57_H3") (pintype "passive+no_connect"))
    )
    (net (code "136") (name "unconnected-(U703B-NC58-PadH12)") (class "Default")
      (node (ref "U703") (pin "H12") (pinfunction "NC58_H12") (pintype "passive+no_connect"))
    )
    (net (code "137") (name "unconnected-(U703B-NC59-PadH13)") (class "Default")
      (node (ref "U703") (pin "H13") (pinfunction "NC59_H13") (pintype "passive+no_connect"))
    )
    (net (code "138") (name "unconnected-(U703B-NC60-PadH14)") (class "Default")
      (node (ref "U703") (pin "H14") (pinfunction "NC60_H14") (pintype "passive+no_connect"))
    )
    (net (code "139") (name "unconnected-(U703B-NC61-PadJ1)") (class "Default")
      (node (ref "U703") (pin "J1") (pinfunction "NC61_J1") (pintype "passive+no_connect"))
    )
    (net (code "140") (name "unconnected-(U703B-NC62-PadJ2)") (class "Default")
      (node (ref "U703") (pin "J2") (pinfunction "NC62_J2") (pintype "passive+no_connect"))
    )
    (net (code "141") (name "unconnected-(U703B-NC63-PadJ3)") (class "Default")
      (node (ref "U703") (pin "J3") (pinfunction "NC63_J3") (pintype "passive+no_connect"))
    )
    (net (code "142") (name "unconnected-(U703B-NC64-PadJ12)") (class "Default")
      (node (ref "U703") (pin "J12") (pinfunction "NC64_J12") (pintype "passive+no_connect"))
    )
    (net (code "143") (name "unconnected-(U703B-NC65-PadJ13)") (class "Default")
      (node (ref "U703") (pin "J13") (pinfunction "NC65_J13") (pintype "passive+no_connect"))
    )
    (net (code "144") (name "unconnected-(U703B-NC66-PadJ14)") (class "Default")
      (node (ref "U703") (pin "J14") (pinfunction "NC66_J14") (pintype "passive+no_connect"))
    )
    (net (code "145") (name "unconnected-(U703B-NC67-PadK1)") (class "Default")
      (node (ref "U703") (pin "K1") (pinfunction "NC67_K1") (pintype "passive+no_connect"))
    )
    (net (code "146") (name "unconnected-(U703B-NC68-PadK2)") (class "Default")
      (node (ref "U703") (pin "K2") (pinfunction "NC68_K2") (pintype "passive+no_connect"))
    )
    (net (code "147") (name "unconnected-(U703B-NC69-PadK3)") (class "Default")
      (node (ref "U703") (pin "K3") (pinfunction "NC69_K3") (pintype "passive+no_connect"))
    )
    (net (code "148") (name "unconnected-(U703B-NC70-PadK12)") (class "Default")
      (node (ref "U703") (pin "K12") (pinfunction "NC70_K12") (pintype "passive+no_connect"))
    )
    (net (code "149") (name "unconnected-(U703B-NC71-PadK13)") (class "Default")
      (node (ref "U703") (pin "K13") (pinfunction "NC71_K13") (pintype "passive+no_connect"))
    )
    (net (code "150") (name "unconnected-(U703B-NC72-PadK14)") (class "Default")
      (node (ref "U703") (pin "K14") (pinfunction "NC72_K14") (pintype "passive+no_connect"))
    )
    (net (code "151") (name "unconnected-(U703B-NC73-PadL1)") (class "Default")
      (node (ref "U703") (pin "L1") (pinfunction "NC73_L1") (pintype "passive+no_connect"))
    )
    (net (code "152") (name "unconnected-(U703B-NC74-PadL2)") (class "Default")
      (node (ref "U703") (pin "L2") (pinfunction "NC74_L2") (pintype "passive+no_connect"))
    )
    (net (code "153") (name "unconnected-(U703B-NC75-PadL3)") (class "Default")
      (node (ref "U703") (pin "L3") (pinfunction "NC75_L3") (pintype "passive+no_connect"))
    )
    (net (code "154") (name "unconnected-(U703B-NC76-PadL12)") (class "Default")
      (node (ref "U703") (pin "L12") (pinfunction "NC76_L12") (pintype "passive+no_connect"))
    )
    (net (code "155") (name "unconnected-(U703B-NC77-PadL13)") (class "Default")
      (node (ref "U703") (pin "L13") (pinfunction "NC77_L13") (pintype "passive+no_connect"))
    )
    (net (code "156") (name "unconnected-(U703B-NC78-PadL14)") (class "Default")
      (node (ref "U703") (pin "L14") (pinfunction "NC78_L14") (pintype "passive+no_connect"))
    )
    (net (code "157") (name "unconnected-(U703B-NC79-PadM1)") (class "Default")
      (node (ref "U703") (pin "M1") (pinfunction "NC79_M1") (pintype "passive+no_connect"))
    )
    (net (code "158") (name "unconnected-(U703B-NC80-PadM2)") (class "Default")
      (node (ref "U703") (pin "M2") (pinfunction "NC80_M2") (pintype "passive+no_connect"))
    )
    (net (code "159") (name "unconnected-(U703B-NC81-PadM3)") (class "Default")
      (node (ref "U703") (pin "M3") (pinfunction "NC81_M3") (pintype "passive+no_connect"))
    )
    (net (code "160") (name "unconnected-(U703B-NC82-PadM7)") (class "Default")
      (node (ref "U703") (pin "M7") (pinfunction "NC82_M7") (pintype "passive+no_connect"))
    )
    (net (code "161") (name "unconnected-(U703B-NC83-PadM8)") (class "Default")
      (node (ref "U703") (pin "M8") (pinfunction "NC83_M8") (pintype "passive+no_connect"))
    )
    (net (code "162") (name "unconnected-(U703B-NC84-PadM9)") (class "Default")
      (node (ref "U703") (pin "M9") (pinfunction "NC84_M9") (pintype "passive+no_connect"))
    )
    (net (code "163") (name "unconnected-(U703B-NC85-PadM10)") (class "Default")
      (node (ref "U703") (pin "M10") (pinfunction "NC85_M10") (pintype "passive+no_connect"))
    )
    (net (code "164") (name "unconnected-(U703B-NC86-PadM11)") (class "Default")
      (node (ref "U703") (pin "M11") (pinfunction "NC86_M11") (pintype "passive+no_connect"))
    )
    (net (code "165") (name "unconnected-(U703B-NC87-PadM12)") (class "Default")
      (node (ref "U703") (pin "M12") (pinfunction "NC87_M12") (pintype "passive+no_connect"))
    )
    (net (code "166") (name "unconnected-(U703B-NC88-PadM13)") (class "Default")
      (node (ref "U703") (pin "M13") (pinfunction "NC88_M13") (pintype "passive+no_connect"))
    )
    (net (code "167") (name "unconnected-(U703B-NC89-PadM14)") (class "Default")
      (node (ref "U703") (pin "M14") (pinfunction "NC89_M14") (pintype "passive+no_connect"))
    )
    (net (code "168") (name "unconnected-(U703B-NC91-PadN3)") (class "Default")
      (node (ref "U703") (pin "N3") (pinfunction "NC91_N3") (pintype "passive+no_connect"))
    )
    (net (code "169") (name "unconnected-(U703B-NC92-PadN6)") (class "Default")
      (node (ref "U703") (pin "N6") (pinfunction "NC92_N6") (pintype "passive+no_connect"))
    )
    (net (code "170") (name "unconnected-(U703B-NC93-PadN7)") (class "Default")
      (node (ref "U703") (pin "N7") (pinfunction "NC93_N7") (pintype "passive+no_connect"))
    )
    (net (code "171") (name "unconnected-(U703B-NC94-PadN8)") (class "Default")
      (node (ref "U703") (pin "N8") (pinfunction "NC94_N8") (pintype "passive+no_connect"))
    )
    (net (code "172") (name "unconnected-(U703B-NC95-PadN9)") (class "Default")
      (node (ref "U703") (pin "N9") (pinfunction "NC95_N9") (pintype "passive+no_connect"))
    )
    (net (code "173") (name "unconnected-(U703B-NC96-PadN10)") (class "Default")
      (node (ref "U703") (pin "N10") (pinfunction "NC96_N10") (pintype "passive+no_connect"))
    )
    (net (code "174") (name "unconnected-(U703B-NC97-PadN11)") (class "Default")
      (node (ref "U703") (pin "N11") (pinfunction "NC97_N11") (pintype "passive+no_connect"))
    )
    (net (code "175") (name "unconnected-(U703B-NC98-PadN12)") (class "Default")
      (node (ref "U703") (pin "N12") (pinfunction "NC98_N12") (pintype "passive+no_connect"))
    )
    (net (code "176") (name "unconnected-(U703B-NC99-PadN13)") (class "Default")
      (node (ref "U703") (pin "N13") (pinfunction "NC99_N13") (pintype "passive+no_connect"))
    )
    (net (code "177") (name "unconnected-(U703B-NC100-PadN14)") (class "Default")
      (node (ref "U703") (pin "N14") (pinfunction "NC100_N14") (pintype "passive+no_connect"))
    )
    (net (code "178") (name "unconnected-(U703B-NC102-PadP2)") (class "Default")
      (node (ref "U703") (pin "P2") (pinfunction "NC102_P2") (pintype "passive+no_connect"))
    )
    (net (code "179") (name "unconnected-(U703B-NC103-PadP7)") (class "Default")
      (node (ref "U703") (pin "P7") (pinfunction "NC103_P7") (pintype "passive+no_connect"))
    )
    (net (code "180") (name "unconnected-(U703B-NC104-PadP8)") (class "Default")
      (node (ref "U703") (pin "P8") (pinfunction "NC104_P8") (pintype "passive+no_connect"))
    )
    (net (code "181") (name "unconnected-(U703B-NC105-PadP9)") (class "Default")
      (node (ref "U703") (pin "P9") (pinfunction "NC105_P9") (pintype "passive+no_connect"))
    )
    (net (code "182") (name "unconnected-(U703B-NC106-PadP11)") (class "Default")
      (node (ref "U703") (pin "P11") (pinfunction "NC106_P11") (pintype "passive+no_connect"))
    )
    (net (code "183") (name "unconnected-(U703B-NC107-PadP12)") (class "Default")
      (node (ref "U703") (pin "P12") (pinfunction "NC107_P12") (pintype "passive+no_connect"))
    )
    (net (code "184") (name "unconnected-(U703B-NC108-PadP13)") (class "Default")
      (node (ref "U703") (pin "P13") (pinfunction "NC108_P13") (pintype "passive+no_connect"))
    )
    (net (code "185") (name "unconnected-(U703B-NC109-PadP14)") (class "Default")
      (node (ref "U703") (pin "P14") (pinfunction "NC109_P14") (pintype "passive+no_connect"))
    )
    (net (code "186") (name "unconnected-(U703B-RFU1-PadA7)") (class "Default")
      (node (ref "U703") (pin "A7") (pinfunction "RFU1_A7") (pintype "passive+no_connect"))
    )
    (net (code "187") (name "unconnected-(U703B-RFU2-PadE5)") (class "Default")
      (node (ref "U703") (pin "E5") (pinfunction "RFU2_E5") (pintype "passive+no_connect"))
    )
    (net (code "188") (name "unconnected-(U703B-RFU3-PadK6)") (class "Default")
      (node (ref "U703") (pin "K6") (pinfunction "RFU3_K6") (pintype "passive+no_connect"))
    )
    (net (code "189") (name "unconnected-(U703B-RFU4-PadK7)") (class "Default")
      (node (ref "U703") (pin "K7") (pinfunction "RFU4_K7") (pintype "passive+no_connect"))
    )
    (net (code "190") (name "unconnected-(U703B-VSF1-PadE8)") (class "Default")
      (node (ref "U703") (pin "E8") (pinfunction "VSF1_E8") (pintype "passive+no_connect"))
    )
    (net (code "191") (name "unconnected-(U703B-VSF2-PadE9)") (class "Default")
      (node (ref "U703") (pin "E9") (pinfunction "VSF2_E9") (pintype "passive+no_connect"))
    )
    (net (code "192") (name "unconnected-(U703B-VSF3-PadE10)") (class "Default")
      (node (ref "U703") (pin "E10") (pinfunction "VSF3_E10") (pintype "passive+no_connect"))
    )
    (net (code "193") (name "unconnected-(U703B-VSF4-PadF10)") (class "Default")
      (node (ref "U703") (pin "F10") (pinfunction "VSF4_F10") (pintype "passive+no_connect"))
    )
    (net (code "194") (name "unconnected-(U703B-VSF5-PadG10)") (class "Default")
      (node (ref "U703") (pin "G10") (pinfunction "VSF5_G10") (pintype "passive+no_connect"))
    )
    (net (code "195") (name "unconnected-(U703B-VSF6-PadK10)") (class "Default")
      (node (ref "U703") (pin "K10") (pinfunction "VSF6_K10") (pintype "passive+no_connect"))
    )
    (net (code "196") (name "unconnected-(U703B-VSF7-PadP10)") (class "Default")
      (node (ref "U703") (pin "P10") (pinfunction "VSF7_P10") (pintype "passive+no_connect"))
    )
  )
)
